# SCH_Robot_2025-06-21_1.net
KiCad netlist of a schematic drawn in EasyEDA
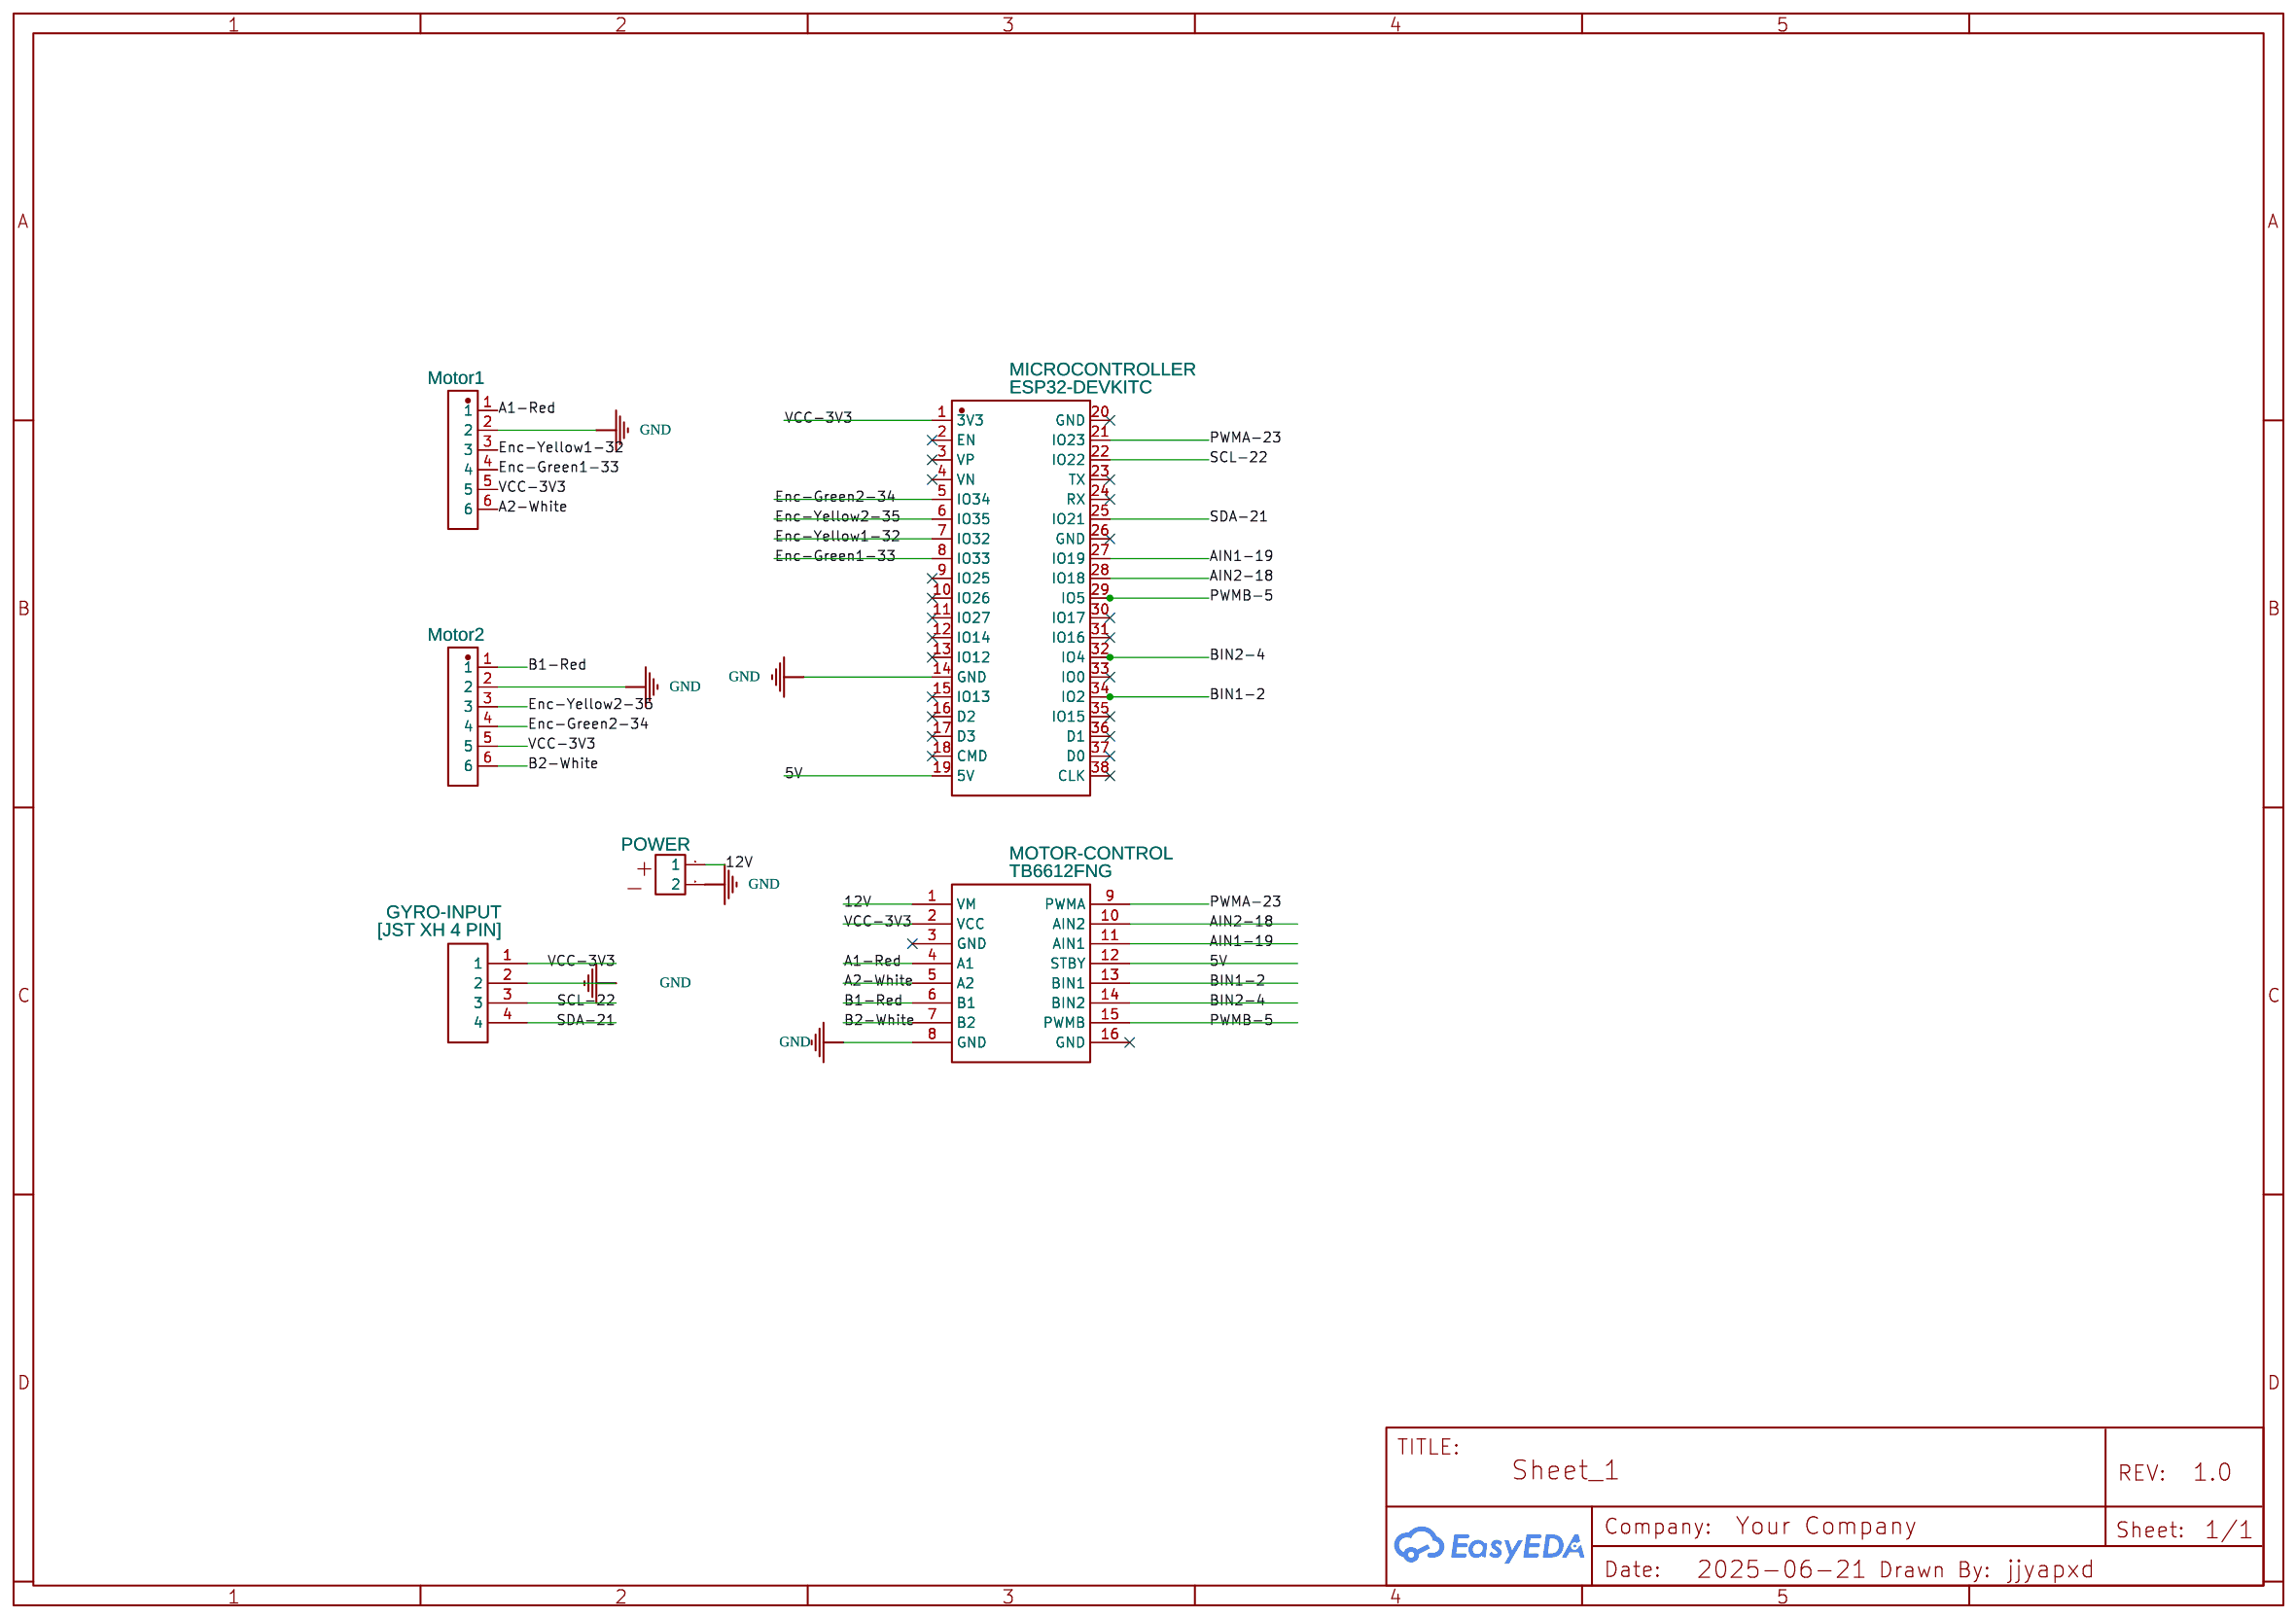
[diagram p0: schematic sheet]

(export (version "E")
  (design (tool "Eeschema 10.0.6"))
  (components
    (comp (ref "GYRO-INPUT") (value "[JST XH 4 PIN]") (libsource (lib "") (part "[JST XH 4 PIN]")))
    (comp (ref "J1") (value "Motor2") (libsource (lib "") (part "XH2.54-6_BAT")))
    (comp (ref "J2") (value "Motor1") (libsource (lib "") (part "XH2.54-6_BAT")))
    (comp (ref "MICROCONTROLLER")
      (value "ESP32-DEVKITC")
      (fields
        (field (name "Manufacturer Part") "ESP32-DevKitC")
        (field (name "Manufacturer") "ESPRESSIF(乐鑫)")
      )
      (libsource (lib "") (part "ESP32-DEVKITC"))
    )
    (comp (ref "MOTOR-CONTROL") (value "TB6612FNG") (libsource (lib "") (part "TB6612FNG")))
    (comp (ref "POWER")
      (value "ZS-Header-F-2.54_1x2")
      (fields (field (name "Manufacturer Part") "56156") (field (name "Manufacturer") "Banggood"))
      (libsource (lib "") (part "ZS-Header-F-2.54_1x2"))
    )
  )
  (nets
    (net (code "1") (name "/5V") (class "Default")
      (node (ref "MICROCONTROLLER") (pin "19") (pinfunction "5V_19") (pintype "unspecified"))
      (node (ref "MOTOR-CONTROL") (pin "12") (pinfunction "STBY_12") (pintype "unspecified"))
    )
    (net (code "2") (name "/12V") (class "Default")
      (node (ref "MOTOR-CONTROL") (pin "1") (pinfunction "VM_1") (pintype "unspecified"))
      (node (ref "POWER") (pin "1") (pinfunction "1_1") (pintype "input"))
    )
    (net (code "3") (name "/A1-Red") (class "Default")
      (node (ref "J2") (pin "1") (pinfunction "1_1") (pintype "unspecified"))
      (node (ref "MOTOR-CONTROL") (pin "4") (pinfunction "A1_4") (pintype "unspecified"))
    )
    (net (code "4") (name "/A2-White") (class "Default")
      (node (ref "J2") (pin "6") (pinfunction "6_6") (pintype "unspecified"))
      (node (ref "MOTOR-CONTROL") (pin "5") (pinfunction "A2_5") (pintype "unspecified"))
    )
    (net (code "5") (name "/AIN1-19") (class "Default")
      (node (ref "MICROCONTROLLER") (pin "27") (pinfunction "IO19_27") (pintype "unspecified"))
      (node (ref "MOTOR-CONTROL") (pin "11") (pinfunction "AIN1_11") (pintype "unspecified"))
    )
    (net (code "6") (name "/AIN2-18") (class "Default")
      (node (ref "MICROCONTROLLER") (pin "28") (pinfunction "IO18_28") (pintype "unspecified"))
      (node (ref "MOTOR-CONTROL") (pin "10") (pinfunction "AIN2_10") (pintype "unspecified"))
    )
    (net (code "7") (name "/B1-Red") (class "Default")
      (node (ref "J1") (pin "1") (pinfunction "1_1") (pintype "unspecified"))
      (node (ref "MOTOR-CONTROL") (pin "6") (pinfunction "B1_6") (pintype "unspecified"))
    )
    (net (code "8") (name "/B2-White") (class "Default")
      (node (ref "J1") (pin "6") (pinfunction "6_6") (pintype "unspecified"))
      (node (ref "MOTOR-CONTROL") (pin "7") (pinfunction "B2_7") (pintype "unspecified"))
    )
    (net (code "9") (name "/BIN1-2") (class "Default")
      (node (ref "MICROCONTROLLER") (pin "34") (pinfunction "IO2_34") (pintype "unspecified"))
      (node (ref "MOTOR-CONTROL") (pin "13") (pinfunction "BIN1_13") (pintype "unspecified"))
    )
    (net (code "10") (name "/BIN2-4") (class "Default")
      (node (ref "MICROCONTROLLER") (pin "32") (pinfunction "IO4_32") (pintype "unspecified"))
      (node (ref "MOTOR-CONTROL") (pin "14") (pinfunction "BIN2_14") (pintype "unspecified"))
    )
    (net (code "11") (name "/Enc-Green1-33") (class "Default")
      (node (ref "J2") (pin "4") (pinfunction "4_4") (pintype "unspecified"))
      (node (ref "MICROCONTROLLER") (pin "8") (pinfunction "IO33_8") (pintype "unspecified"))
    )
    (net (code "12") (name "/Enc-Green2-34") (class "Default")
      (node (ref "J1") (pin "4") (pinfunction "4_4") (pintype "unspecified"))
      (node (ref "MICROCONTROLLER") (pin "5") (pinfunction "IO34_5") (pintype "unspecified"))
    )
    (net (code "13") (name "/Enc-Yellow1-32") (class "Default")
      (node (ref "J2") (pin "3") (pinfunction "3_3") (pintype "unspecified"))
      (node (ref "MICROCONTROLLER") (pin "7") (pinfunction "IO32_7") (pintype "unspecified"))
    )
    (net (code "14") (name "/Enc-Yellow2-35") (class "Default")
      (node (ref "J1") (pin "3") (pinfunction "3_3") (pintype "unspecified"))
      (node (ref "MICROCONTROLLER") (pin "6") (pinfunction "IO35_6") (pintype "unspecified"))
    )
    (net (code "15") (name "/PWMA-23") (class "Default")
      (node (ref "MICROCONTROLLER") (pin "21") (pinfunction "IO23_21") (pintype "unspecified"))
      (node (ref "MOTOR-CONTROL") (pin "9") (pinfunction "PWMA_9") (pintype "unspecified"))
    )
    (net (code "16") (name "/PWMB-5") (class "Default")
      (node (ref "MICROCONTROLLER") (pin "29") (pinfunction "IO5_29") (pintype "unspecified"))
      (node (ref "MOTOR-CONTROL") (pin "15") (pinfunction "PWMB_15") (pintype "unspecified"))
    )
    (net (code "17") (name "/SCL-22") (class "Default")
      (node (ref "GYRO-INPUT") (pin "3") (pinfunction "3_3") (pintype "unspecified"))
      (node (ref "MICROCONTROLLER") (pin "22") (pinfunction "IO22_22") (pintype "unspecified"))
    )
    (net (code "18") (name "/SDA-21") (class "Default")
      (node (ref "GYRO-INPUT") (pin "4") (pinfunction "4_4") (pintype "unspecified"))
      (node (ref "MICROCONTROLLER") (pin "25") (pinfunction "IO21_25") (pintype "unspecified"))
    )
    (net (code "19") (name "/VCC-3V3") (class "Default")
      (node (ref "GYRO-INPUT") (pin "1") (pinfunction "1_1") (pintype "unspecified"))
      (node (ref "J1") (pin "5") (pinfunction "5_5") (pintype "unspecified"))
      (node (ref "J2") (pin "5") (pinfunction "5_5") (pintype "unspecified"))
      (node (ref "MICROCONTROLLER") (pin "1") (pinfunction "3V3_1") (pintype "unspecified"))
      (node (ref "MOTOR-CONTROL") (pin "2") (pinfunction "VCC_2") (pintype "unspecified"))
    )
    (net (code "20") (name "GND") (class "Default")
      (node (ref "GYRO-INPUT") (pin "2") (pinfunction "2_2") (pintype "unspecified"))
      (node (ref "J1") (pin "2") (pinfunction "2_2") (pintype "unspecified"))
      (node (ref "J2") (pin "2") (pinfunction "2_2") (pintype "unspecified"))
      (node (ref "MICROCONTROLLER") (pin "14") (pinfunction "GND_14") (pintype "unspecified"))
      (node (ref "MOTOR-CONTROL") (pin "8") (pinfunction "GND_8") (pintype "unspecified"))
      (node (ref "POWER") (pin "2") (pinfunction "2_2") (pintype "input"))
    )
    (net (code "21") (name "unconnected-(MICROCONTROLLER-CLK-Pad38)") (class "Default")
      (node (ref "MICROCONTROLLER") (pin "38") (pinfunction "CLK_38") (pintype "unspecified+no_connect"))
    )
    (net (code "22") (name "unconnected-(MICROCONTROLLER-CMD-Pad18)") (class "Default")
      (node (ref "MICROCONTROLLER") (pin "18") (pinfunction "CMD_18") (pintype "unspecified+no_connect"))
    )
    (net (code "23") (name "unconnected-(MICROCONTROLLER-D0-Pad37)") (class "Default")
      (node (ref "MICROCONTROLLER") (pin "37") (pinfunction "D0_37") (pintype "unspecified+no_connect"))
    )
    (net (code "24") (name "unconnected-(MICROCONTROLLER-D1-Pad36)") (class "Default")
      (node (ref "MICROCONTROLLER") (pin "36") (pinfunction "D1_36") (pintype "unspecified+no_connect"))
    )
    (net (code "25") (name "unconnected-(MICROCONTROLLER-D2-Pad16)") (class "Default")
      (node (ref "MICROCONTROLLER") (pin "16") (pinfunction "D2_16") (pintype "unspecified+no_connect"))
    )
    (net (code "26") (name "unconnected-(MICROCONTROLLER-D3-Pad17)") (class "Default")
      (node (ref "MICROCONTROLLER") (pin "17") (pinfunction "D3_17") (pintype "unspecified+no_connect"))
    )
    (net (code "27") (name "unconnected-(MICROCONTROLLER-EN-Pad2)") (class "Default")
      (node (ref "MICROCONTROLLER") (pin "2") (pinfunction "EN_2") (pintype "unspecified+no_connect"))
    )
    (net (code "28") (name "unconnected-(MICROCONTROLLER-GND-Pad20)") (class "Default")
      (node (ref "MICROCONTROLLER") (pin "20") (pinfunction "GND_20") (pintype "unspecified+no_connect"))
    )
    (net (code "29") (name "unconnected-(MICROCONTROLLER-GND-Pad26)") (class "Default")
      (node (ref "MICROCONTROLLER") (pin "26") (pinfunction "GND_26") (pintype "unspecified+no_connect"))
    )
    (net (code "30") (name "unconnected-(MICROCONTROLLER-IO0-Pad33)") (class "Default")
      (node (ref "MICROCONTROLLER") (pin "33") (pinfunction "IO0_33") (pintype "unspecified+no_connect"))
    )
    (net (code "31") (name "unconnected-(MICROCONTROLLER-IO12-Pad13)") (class "Default")
      (node (ref "MICROCONTROLLER") (pin "13") (pinfunction "IO12_13") (pintype "unspecified+no_connect"))
    )
    (net (code "32") (name "unconnected-(MICROCONTROLLER-IO13-Pad15)") (class "Default")
      (node (ref "MICROCONTROLLER") (pin "15") (pinfunction "IO13_15") (pintype "unspecified+no_connect"))
    )
    (net (code "33") (name "unconnected-(MICROCONTROLLER-IO14-Pad12)") (class "Default")
      (node (ref "MICROCONTROLLER") (pin "12") (pinfunction "IO14_12") (pintype "unspecified+no_connect"))
    )
    (net (code "34") (name "unconnected-(MICROCONTROLLER-IO15-Pad35)") (class "Default")
      (node (ref "MICROCONTROLLER") (pin "35") (pinfunction "IO15_35") (pintype "unspecified+no_connect"))
    )
    (net (code "35") (name "unconnected-(MICROCONTROLLER-IO16-Pad31)") (class "Default")
      (node (ref "MICROCONTROLLER") (pin "31") (pinfunction "IO16_31") (pintype "unspecified+no_connect"))
    )
    (net (code "36") (name "unconnected-(MICROCONTROLLER-IO17-Pad30)") (class "Default")
      (node (ref "MICROCONTROLLER") (pin "30") (pinfunction "IO17_30") (pintype "unspecified+no_connect"))
    )
    (net (code "37") (name "unconnected-(MICROCONTROLLER-IO25-Pad9)") (class "Default")
      (node (ref "MICROCONTROLLER") (pin "9") (pinfunction "IO25_9") (pintype "unspecified+no_connect"))
    )
    (net (code "38") (name "unconnected-(MICROCONTROLLER-IO26-Pad10)") (class "Default")
      (node (ref "MICROCONTROLLER") (pin "10") (pinfunction "IO26_10") (pintype "unspecified+no_connect"))
    )
    (net (code "39") (name "unconnected-(MICROCONTROLLER-IO27-Pad11)") (class "Default")
      (node (ref "MICROCONTROLLER") (pin "11") (pinfunction "IO27_11") (pintype "unspecified+no_connect"))
    )
    (net (code "40") (name "unconnected-(MICROCONTROLLER-RX-Pad24)") (class "Default")
      (node (ref "MICROCONTROLLER") (pin "24") (pinfunction "RX_24") (pintype "unspecified+no_connect"))
    )
    (net (code "41") (name "unconnected-(MICROCONTROLLER-TX-Pad23)") (class "Default")
      (node (ref "MICROCONTROLLER") (pin "23") (pinfunction "TX_23") (pintype "unspecified+no_connect"))
    )
    (net (code "42") (name "unconnected-(MICROCONTROLLER-VN-Pad4)") (class "Default")
      (node (ref "MICROCONTROLLER") (pin "4") (pinfunction "VN_4") (pintype "unspecified+no_connect"))
    )
    (net (code "43") (name "unconnected-(MICROCONTROLLER-VP-Pad3)") (class "Default")
      (node (ref "MICROCONTROLLER") (pin "3") (pinfunction "VP_3") (pintype "unspecified+no_connect"))
    )
    (net (code "44") (name "unconnected-(MOTOR-CONTROL-GND-Pad3)") (class "Default")
      (node (ref "MOTOR-CONTROL") (pin "3") (pinfunction "GND_3") (pintype "unspecified+no_connect"))
    )
    (net (code "45") (name "unconnected-(MOTOR-CONTROL-GND-Pad16)") (class "Default")
      (node (ref "MOTOR-CONTROL") (pin "16") (pinfunction "GND_16") (pintype "unspecified+no_connect"))
    )
  )
)
